# bot_aux.net
KiCad netlist of a schematic drawn in Altium Designer
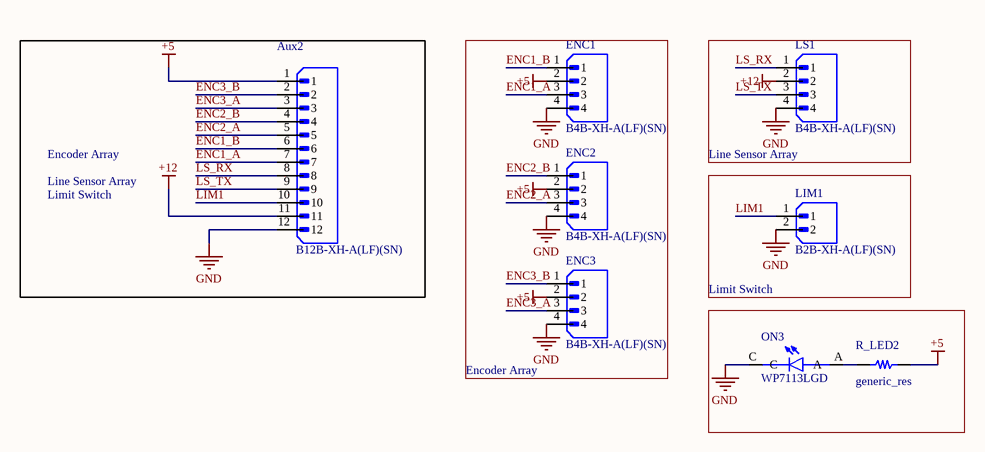
[diagram p0: bot_aux.SchDoc]

(export (version "E")
  (design (tool "Eeschema 10.0.6"))
  (components
    (comp (ref "Aux2")
      (value "B12B-XH-A(LF)(SN)")
      (footprint "JST_B12B-XH-A(LF)(SN)")
      (description "Connector Header Through Hole 12 position 0.098 (2.50mm)")
      (fields (field (name "MF") "JST Sales"))
      (libsource (lib "CSD Robocon Workspace") (part "B12B-XH-A(LF)(SN)"))
    )
    (comp (ref "ENC1")
      (value "B4B-XH-A(LF)(SN)")
      (footprint "JST_B4B-XH-A(LF)(SN)")
      (description "Connector Header Through Hole 4 position 0.098 (2.50mm)")
      (fields (field (name "MF") "JST Sales"))
      (libsource (lib "CSD Robocon Workspace") (part "B4B-XH-A(LF)(SN)"))
    )
    (comp (ref "ENC2")
      (value "B4B-XH-A(LF)(SN)")
      (footprint "JST_B4B-XH-A(LF)(SN)")
      (description "Connector Header Through Hole 4 position 0.098 (2.50mm)")
      (fields (field (name "MF") "JST Sales"))
      (libsource (lib "CSD Robocon Workspace") (part "B4B-XH-A(LF)(SN)"))
    )
    (comp (ref "ENC3")
      (value "B4B-XH-A(LF)(SN)")
      (footprint "JST_B4B-XH-A(LF)(SN)")
      (description "Connector Header Through Hole 4 position 0.098 (2.50mm)")
      (fields (field (name "MF") "JST Sales"))
      (libsource (lib "CSD Robocon Workspace") (part "B4B-XH-A(LF)(SN)"))
    )
    (comp (ref "LIM1")
      (value "B2B-XH-A(LF)(SN)")
      (footprint "JST_B2B-XH-A(LF)(SN)")
      (description "Connector Header Through Hole 2 position 0.098 (2.50mm)")
      (fields (field (name "MF") "JST Sales America Inc."))
      (libsource (lib "CSD Robocon Workspace") (part "B2B-XH-A(LF)(SN)"))
    )
    (comp (ref "LS1")
      (value "B4B-XH-A(LF)(SN)")
      (footprint "JST_B4B-XH-A(LF)(SN)")
      (description "Connector Header Through Hole 4 position 0.098 (2.50mm)")
      (fields (field (name "MF") "JST Sales"))
      (libsource (lib "CSD Robocon Workspace") (part "B4B-XH-A(LF)(SN)"))
    )
    (comp (ref "ON3")
      (value "WP7113LGD")
      (footprint "LED_WP7113LGD")
      (description "Green 568nm LED Indication - Discrete 1.9V Radial")
      (fields (field (name "MF") "Kingbright"))
      (libsource (lib "CSD Robocon Workspace") (part "WP7113LGD"))
    )
    (comp (ref "R_LED2")
      (value "generic_res")
      (footprint "generic_res_footprint")
      (description "Generic through hole resistor")
      (libsource (lib "CSD Robocon Workspace") (part "generic_res"))
    )
  )
  (nets
    (net (code "1") (name "+5") (class "Default")
      (node (ref "Aux2") (pin "1") (pinfunction "1_1") (pintype "passive"))
      (node (ref "ENC1") (pin "2") (pinfunction "2_2") (pintype "passive"))
      (node (ref "ENC2") (pin "2") (pinfunction "2_2") (pintype "passive"))
      (node (ref "ENC3") (pin "2") (pinfunction "2_2") (pintype "passive"))
      (node (ref "R_LED2") (pin "2") (pinfunction "2_2") (pintype "passive"))
    )
    (net (code "2") (name "+12") (class "Default")
      (node (ref "Aux2") (pin "11") (pinfunction "11_11") (pintype "passive"))
      (node (ref "LS1") (pin "2") (pinfunction "2_2") (pintype "passive"))
    )
    (net (code "3") (name "/ENC1_A") (class "Default")
      (node (ref "Aux2") (pin "7") (pinfunction "7_7") (pintype "passive"))
      (node (ref "ENC1") (pin "3") (pinfunction "3_3") (pintype "passive"))
    )
    (net (code "4") (name "/ENC1_B") (class "Default")
      (node (ref "Aux2") (pin "6") (pinfunction "6_6") (pintype "passive"))
      (node (ref "ENC1") (pin "1") (pinfunction "1_1") (pintype "passive"))
    )
    (net (code "5") (name "/ENC2_A") (class "Default")
      (node (ref "Aux2") (pin "5") (pinfunction "5_5") (pintype "passive"))
      (node (ref "ENC2") (pin "3") (pinfunction "3_3") (pintype "passive"))
    )
    (net (code "6") (name "/ENC2_B") (class "Default")
      (node (ref "Aux2") (pin "4") (pinfunction "4_4") (pintype "passive"))
      (node (ref "ENC2") (pin "1") (pinfunction "1_1") (pintype "passive"))
    )
    (net (code "7") (name "/ENC3_A") (class "Default")
      (node (ref "Aux2") (pin "3") (pinfunction "3_3") (pintype "passive"))
      (node (ref "ENC3") (pin "3") (pinfunction "3_3") (pintype "passive"))
    )
    (net (code "8") (name "/ENC3_B") (class "Default")
      (node (ref "Aux2") (pin "2") (pinfunction "2_2") (pintype "passive"))
      (node (ref "ENC3") (pin "1") (pinfunction "1_1") (pintype "passive"))
    )
    (net (code "9") (name "/LIM1") (class "Default")
      (node (ref "Aux2") (pin "10") (pinfunction "10_10") (pintype "passive"))
      (node (ref "LIM1") (pin "1") (pinfunction "1_1") (pintype "passive"))
    )
    (net (code "10") (name "/LS_RX") (class "Default")
      (node (ref "Aux2") (pin "8") (pinfunction "8_8") (pintype "passive"))
      (node (ref "LS1") (pin "1") (pinfunction "1_1") (pintype "passive"))
    )
    (net (code "11") (name "/LS_TX") (class "Default")
      (node (ref "Aux2") (pin "9") (pinfunction "9_9") (pintype "passive"))
      (node (ref "LS1") (pin "3") (pinfunction "3_3") (pintype "passive"))
    )
    (net (code "12") (name "GND") (class "Default")
      (node (ref "Aux2") (pin "12") (pinfunction "12_12") (pintype "passive"))
      (node (ref "ENC1") (pin "4") (pinfunction "4_4") (pintype "passive"))
      (node (ref "ENC2") (pin "4") (pinfunction "4_4") (pintype "passive"))
      (node (ref "ENC3") (pin "4") (pinfunction "4_4") (pintype "passive"))
      (node (ref "LIM1") (pin "2") (pinfunction "2_2") (pintype "passive"))
      (node (ref "LS1") (pin "4") (pinfunction "4_4") (pintype "passive"))
      (node (ref "ON3") (pin "C") (pinfunction "C_C") (pintype "passive"))
    )
    (net (code "13") (name "Net-(ON3-PadA)") (class "Default")
      (node (ref "ON3") (pin "A") (pinfunction "A_A") (pintype "passive"))
      (node (ref "R_LED2") (pin "1") (pinfunction "1_1") (pintype "passive"))
    )
  )
)
